# plug-v18.net
KiCad netlist of a schematic drawn in EAGLE
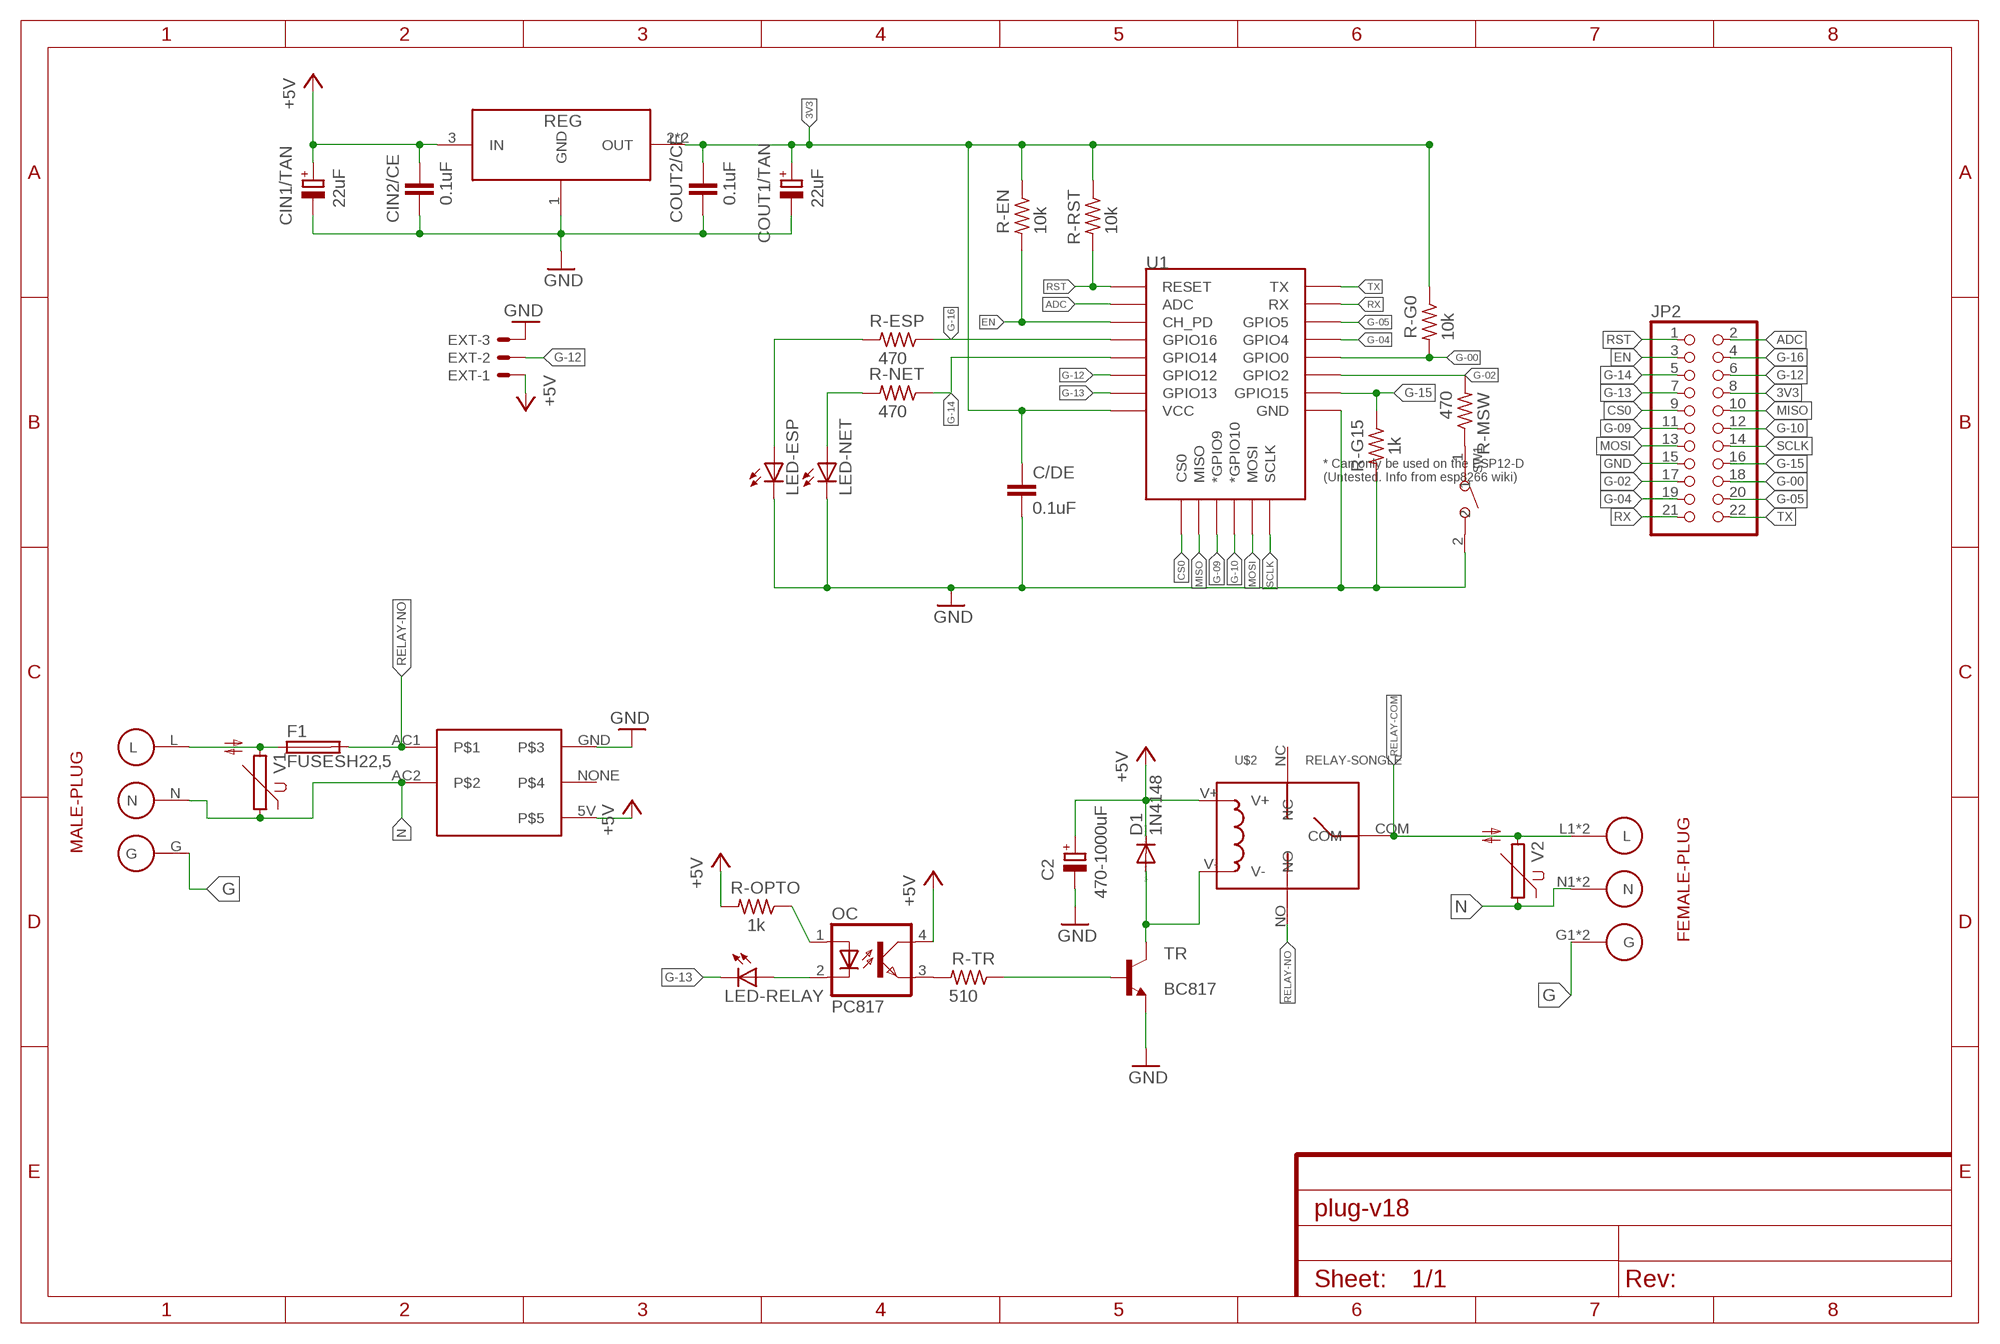
[diagram p0: schematic, sheet 1]

(export (version "E")
  (design (tool "Eeschema 10.0.6"))
  (components
    (comp (ref "C/DE")
      (value "0.1uF")
      (footprint "eagle-import:C0805")
      (libsource (lib "eagle-import") (part "C-EUC0805"))
    )
    (comp (ref "C2")
      (value "470-1000uF")
      (footprint "eagle-import:E3,5-8")
      (libsource (lib "eagle-import") (part "CPOL-EUE3.5-8"))
    )
    (comp (ref "CIN1/TAN")
      (value "22uF")
      (footprint "eagle-import:B_3528-21R")
      (libsource (lib "eagle-import") (part "CPOL-EUB/3528-21R"))
    )
    (comp (ref "CIN2/CE")
      (value "0.1uF")
      (footprint "eagle-import:C0805K")
      (libsource (lib "eagle-import") (part "C-EUC0805K"))
    )
    (comp (ref "COUT1/TAN")
      (value "22uF")
      (footprint "eagle-import:B_3528-21R")
      (libsource (lib "eagle-import") (part "CPOL-EUB/3528-21R"))
    )
    (comp (ref "COUT2/CE")
      (value "0.1uF")
      (footprint "eagle-import:C0805K")
      (libsource (lib "eagle-import") (part "C-EUC0805K"))
    )
    (comp (ref "D1")
      (value "1N4148")
      (footprint "eagle-import:DO35-7")
      (libsource (lib "eagle-import") (part "1N4148DO35-7"))
    )
    (comp (ref "EXT")
      (value "53048-03")
      (footprint "eagle-import:53048-03")
      (fields (field (name "MF") "WALDOM/MOLEX") (field (name "MPN") "53048-0310"))
      (libsource (lib "eagle-import") (part "53?-03048"))
    )
    (comp (ref "F1")
      (value "FUSESH22,5")
      (footprint "eagle-import:SH22,5")
      (libsource (lib "eagle-import") (part "FUSESH22,5"))
    )
    (comp (ref "JP2")
      (value "PINHD-2X11")
      (footprint "eagle-import:2X11")
      (libsource (lib "eagle-import") (part "PINHD-2X11"))
    )
    (comp (ref "LED-ESP")
      (value "LEDCHIPLED_0805")
      (footprint "eagle-import:CHIPLED_0805")
      (libsource (lib "eagle-import") (part "LEDCHIPLED_0805"))
    )
    (comp (ref "LED-NET")
      (value "LEDCHIPLED_0805")
      (footprint "eagle-import:CHIPLED_0805")
      (libsource (lib "eagle-import") (part "LEDCHIPLED_0805"))
    )
    (comp (ref "LED-RELAY")
      (value "LEDCHIPLED_0805")
      (footprint "eagle-import:CHIPLED_0805")
      (libsource (lib "eagle-import") (part "LEDCHIPLED_0805"))
    )
    (comp (ref "OC")
      (value "PC817")
      (footprint "eagle-import:DIL04")
      (fields (field (name "MPN") "PC817X4J000F"))
      (libsource (lib "eagle-import") (part "PC817"))
    )
    (comp (ref "R-EN")
      (value "10k")
      (footprint "eagle-import:M0805")
      (libsource (lib "eagle-import") (part "R-US_M0805"))
    )
    (comp (ref "R-ESP")
      (value "470")
      (footprint "eagle-import:M0805")
      (libsource (lib "eagle-import") (part "R-US_M0805"))
    )
    (comp (ref "R-G0")
      (value "10k")
      (footprint "eagle-import:M0805")
      (libsource (lib "eagle-import") (part "R-US_M0805"))
    )
    (comp (ref "R-G15")
      (value "1k")
      (footprint "eagle-import:M0805")
      (libsource (lib "eagle-import") (part "R-US_M0805"))
    )
    (comp (ref "R-MSW")
      (value "470")
      (footprint "eagle-import:M0805")
      (libsource (lib "eagle-import") (part "R-US_M0805"))
    )
    (comp (ref "R-NET")
      (value "470")
      (footprint "eagle-import:M0805")
      (libsource (lib "eagle-import") (part "R-US_M0805"))
    )
    (comp (ref "R-OPTO")
      (value "1k")
      (footprint "eagle-import:M0805")
      (libsource (lib "eagle-import") (part "R-US_M0805"))
    )
    (comp (ref "R-RST")
      (value "10k")
      (footprint "eagle-import:M0805")
      (libsource (lib "eagle-import") (part "R-US_M0805"))
    )
    (comp (ref "R-TR")
      (value "510")
      (footprint "eagle-import:M0805")
      (libsource (lib "eagle-import") (part "R-US_M0805"))
    )
    (comp (ref "REG")
      (value "AMS1117-3.3")
      (footprint "eagle-import:SOT-223")
      (libsource (lib "eagle-import") (part "AMS1117-3.3"))
    )
    (comp (ref "SW1")
      (value "DIP-BUTTON(2P-6.0X3.0X4.3MM)-TS-1101F")
      (footprint "eagle-import:SW2-5.0-6.0X3.0X4.3MM")
      (libsource (lib "eagle-import") (part "DIP-BUTTON(2P-6.0X3.0X4.3MM)-TS-1101F"))
    )
    (comp (ref "TR")
      (value "BC817")
      (footprint "eagle-import:SOT23-BEC")
      (libsource (lib "eagle-import") (part "BC817SMD-16"))
    )
    (comp (ref "U$2")
      (value "RELAY-SONGLE")
      (footprint "eagle-import:RELAY-SONGLE")
      (libsource (lib "eagle-import") (part "RELAY-SONGLE"))
    )
    (comp (ref "U$3")
      (value "MALE-PLUG")
      (footprint "eagle-import:MALE-PLUG")
      (libsource (lib "eagle-import") (part "MALE-PLUG"))
    )
    (comp (ref "U$4")
      (value "POWERSUPPLY-5V-700MA")
      (footprint "eagle-import:POWERSUPPLY-5V-700MA")
      (libsource (lib "eagle-import") (part "POWERSUPPLY-5V-700MA"))
    )
    (comp (ref "U$5")
      (value "FEMALE-PLUG")
      (footprint "eagle-import:FEMALE-PLUG")
      (libsource (lib "eagle-import") (part "FEMALE-PLUG"))
    )
    (comp (ref "U1")
      (value "ESP12ESMD")
      (footprint "eagle-import:ESP12E-SMD")
      (libsource (lib "eagle-import") (part "ESP12ESMD"))
    )
    (comp (ref "V1")
      (value "S14K11")
      (footprint "eagle-import:S14K11")
      (libsource (lib "eagle-import") (part "S14K11"))
    )
    (comp (ref "V2")
      (value "S14K11")
      (footprint "eagle-import:S14K11")
      (libsource (lib "eagle-import") (part "S14K11"))
    )
  )
  (nets
    (net (code "1") (name "+5V") (class "Default")
      (node (ref "C2") (pin "+") (pinfunction "+_+") (pintype "passive"))
      (node (ref "CIN1/TAN") (pin "+") (pinfunction "+_+") (pintype "passive"))
      (node (ref "CIN2/CE") (pin "1") (pinfunction "1_1") (pintype "passive"))
      (node (ref "D1") (pin "C") (pinfunction "C_C") (pintype "passive"))
      (node (ref "EXT") (pin "1") (pinfunction "S_1") (pintype "passive"))
      (node (ref "OC") (pin "4") (pinfunction "COL_4") (pintype "passive"))
      (node (ref "R-OPTO") (pin "2") (pinfunction "2_2") (pintype "passive"))
      (node (ref "REG") (pin "3") (pinfunction "IN_3") (pintype "input"))
      (node (ref "U$2") (pin "V+") (pinfunction "V+_V+") (pintype "bidirectional"))
      (node (ref "U$4") (pin "5V") (pinfunction "P$5_5V") (pintype "bidirectional"))
    )
    (net (code "2") (name "3V3") (class "Default")
      (node (ref "C/DE") (pin "1") (pinfunction "1_1") (pintype "passive"))
      (node (ref "COUT1/TAN") (pin "+") (pinfunction "+_+") (pintype "passive"))
      (node (ref "COUT2/CE") (pin "1") (pinfunction "1_1") (pintype "passive"))
      (node (ref "JP2") (pin "8") (pinfunction "8_8") (pintype "passive"))
      (node (ref "R-EN") (pin "1") (pinfunction "1_1") (pintype "passive"))
      (node (ref "R-G0") (pin "1") (pinfunction "1_1") (pintype "passive"))
      (node (ref "R-RST") (pin "1") (pinfunction "1_1") (pintype "passive"))
      (node (ref "REG") (pin "2") (pinfunction "OUT_2") (pintype "output"))
      (node (ref "REG") (pin "4") (pinfunction "OUT_4") (pintype "output"))
      (node (ref "U1") (pin "VCC") (pinfunction "VCC_VCC") (pintype "bidirectional"))
    )
    (net (code "3") (name "ADC") (class "Default")
      (node (ref "JP2") (pin "2") (pinfunction "2_2") (pintype "passive"))
      (node (ref "U1") (pin "ADC") (pinfunction "ADC_ADC") (pintype "bidirectional"))
    )
    (net (code "4") (name "CS0") (class "Default")
      (node (ref "JP2") (pin "9") (pinfunction "9_9") (pintype "passive"))
      (node (ref "U1") (pin "CS0") (pinfunction "CS0_CS0") (pintype "bidirectional"))
    )
    (net (code "5") (name "EN") (class "Default")
      (node (ref "JP2") (pin "3") (pinfunction "3_3") (pintype "passive"))
      (node (ref "R-EN") (pin "2") (pinfunction "2_2") (pintype "passive"))
      (node (ref "U1") (pin "CH_PD") (pinfunction "CH_PD_CH_PD") (pintype "bidirectional"))
    )
    (net (code "6") (name "G") (class "Default")
      (node (ref "U$3") (pin "G") (pinfunction "G_G") (pintype "bidirectional"))
      (node (ref "U$5") (pin "G1") (pinfunction "G_G1") (pintype "bidirectional"))
      (node (ref "U$5") (pin "G2") (pinfunction "G_G2") (pintype "bidirectional"))
    )
    (net (code "7") (name "G-00") (class "Default")
      (node (ref "JP2") (pin "18") (pinfunction "18_18") (pintype "passive"))
      (node (ref "R-G0") (pin "2") (pinfunction "2_2") (pintype "passive"))
      (node (ref "U1") (pin "GPIO0") (pinfunction "GPIO0_GPIO0") (pintype "bidirectional"))
    )
    (net (code "8") (name "G-02") (class "Default")
      (node (ref "JP2") (pin "17") (pinfunction "17_17") (pintype "passive"))
      (node (ref "R-MSW") (pin "2") (pinfunction "2_2") (pintype "passive"))
      (node (ref "U1") (pin "GPIO2") (pinfunction "GPIO2_GPIO2") (pintype "bidirectional"))
    )
    (net (code "9") (name "G-04") (class "Default")
      (node (ref "JP2") (pin "19") (pinfunction "19_19") (pintype "passive"))
      (node (ref "U1") (pin "GPIO4") (pinfunction "GPIO4_GPIO4") (pintype "bidirectional"))
    )
    (net (code "10") (name "G-05") (class "Default")
      (node (ref "JP2") (pin "20") (pinfunction "20_20") (pintype "passive"))
      (node (ref "U1") (pin "GPIO5") (pinfunction "GPIO5_GPIO5") (pintype "bidirectional"))
    )
    (net (code "11") (name "G-09") (class "Default")
      (node (ref "JP2") (pin "11") (pinfunction "11_11") (pintype "passive"))
      (node (ref "U1") (pin "GPIO9") (pinfunction "*GPIO9_GPIO9") (pintype "bidirectional"))
    )
    (net (code "12") (name "G-10") (class "Default")
      (node (ref "JP2") (pin "12") (pinfunction "12_12") (pintype "passive"))
      (node (ref "U1") (pin "GPIO10") (pinfunction "*GPIO10_GPIO10") (pintype "bidirectional"))
    )
    (net (code "13") (name "G-12") (class "Default")
      (node (ref "EXT") (pin "2") (pinfunction "S_2") (pintype "passive"))
      (node (ref "JP2") (pin "6") (pinfunction "6_6") (pintype "passive"))
      (node (ref "U1") (pin "GPIO12") (pinfunction "GPIO12_GPIO12") (pintype "bidirectional"))
    )
    (net (code "14") (name "G-13") (class "Default")
      (node (ref "JP2") (pin "7") (pinfunction "7_7") (pintype "passive"))
      (node (ref "LED-RELAY") (pin "C") (pinfunction "C_C") (pintype "passive"))
      (node (ref "U1") (pin "GPIO13") (pinfunction "GPIO13_GPIO13") (pintype "bidirectional"))
    )
    (net (code "15") (name "G-14") (class "Default")
      (node (ref "JP2") (pin "5") (pinfunction "5_5") (pintype "passive"))
      (node (ref "R-NET") (pin "1") (pinfunction "1_1") (pintype "passive"))
      (node (ref "U1") (pin "GPIO14") (pinfunction "GPIO14_GPIO14") (pintype "bidirectional"))
    )
    (net (code "16") (name "G-15") (class "Default")
      (node (ref "JP2") (pin "16") (pinfunction "16_16") (pintype "passive"))
      (node (ref "R-G15") (pin "1") (pinfunction "1_1") (pintype "passive"))
      (node (ref "U1") (pin "GPIO15") (pinfunction "GPIO15_GPIO15") (pintype "bidirectional"))
    )
    (net (code "17") (name "G-16") (class "Default")
      (node (ref "JP2") (pin "4") (pinfunction "4_4") (pintype "passive"))
      (node (ref "R-ESP") (pin "1") (pinfunction "1_1") (pintype "passive"))
      (node (ref "U1") (pin "GPIO16") (pinfunction "GPIO16_GPIO16") (pintype "bidirectional"))
    )
    (net (code "18") (name "GND") (class "Default")
      (node (ref "C/DE") (pin "2") (pinfunction "2_2") (pintype "passive"))
      (node (ref "C2") (pin "-") (pinfunction "-_-") (pintype "passive"))
      (node (ref "CIN1/TAN") (pin "-") (pinfunction "-_-") (pintype "passive"))
      (node (ref "CIN2/CE") (pin "2") (pinfunction "2_2") (pintype "passive"))
      (node (ref "COUT1/TAN") (pin "-") (pinfunction "-_-") (pintype "passive"))
      (node (ref "COUT2/CE") (pin "2") (pinfunction "2_2") (pintype "passive"))
      (node (ref "EXT") (pin "3") (pinfunction "S_3") (pintype "passive"))
      (node (ref "JP2") (pin "15") (pinfunction "15_15") (pintype "passive"))
      (node (ref "LED-ESP") (pin "C") (pinfunction "C_C") (pintype "passive"))
      (node (ref "LED-NET") (pin "C") (pinfunction "C_C") (pintype "passive"))
      (node (ref "R-G15") (pin "2") (pinfunction "2_2") (pintype "passive"))
      (node (ref "REG") (pin "1") (pinfunction "GND_1") (pintype "passive"))
      (node (ref "SW1") (pin "2") (pinfunction "2_2") (pintype "bidirectional"))
      (node (ref "TR") (pin "E") (pinfunction "E_E") (pintype "passive"))
      (node (ref "U$4") (pin "GND") (pinfunction "P$3_GND") (pintype "bidirectional"))
      (node (ref "U1") (pin "GND") (pinfunction "GND_GND") (pintype "bidirectional"))
    )
    (net (code "19") (name "MISO") (class "Default")
      (node (ref "JP2") (pin "10") (pinfunction "10_10") (pintype "passive"))
      (node (ref "U1") (pin "MISO") (pinfunction "MISO_MISO") (pintype "bidirectional"))
    )
    (net (code "20") (name "MOSI") (class "Default")
      (node (ref "JP2") (pin "13") (pinfunction "13_13") (pintype "passive"))
      (node (ref "U1") (pin "MOSI") (pinfunction "MOSI_MOSI") (pintype "bidirectional"))
    )
    (net (code "21") (name "N") (class "Default")
      (node (ref "U$3") (pin "N") (pinfunction "N_N") (pintype "bidirectional"))
      (node (ref "U$4") (pin "AC2") (pinfunction "P$2_AC2") (pintype "bidirectional"))
      (node (ref "U$5") (pin "N1") (pinfunction "N_N1") (pintype "bidirectional"))
      (node (ref "U$5") (pin "N2") (pinfunction "N_N2") (pintype "bidirectional"))
      (node (ref "V1") (pin "1") (pinfunction "1_1") (pintype "passive"))
      (node (ref "V2") (pin "1") (pinfunction "1_1") (pintype "passive"))
    )
    (net (code "22") (name "Net-(D1-PadA)") (class "Default")
      (node (ref "D1") (pin "A") (pinfunction "A_A") (pintype "passive"))
      (node (ref "TR") (pin "C") (pinfunction "C_C") (pintype "passive"))
      (node (ref "U$2") (pin "V-") (pinfunction "V-_V-") (pintype "bidirectional"))
    )
    (net (code "23") (name "Net-(F1-Pad1)") (class "Default")
      (node (ref "F1") (pin "1") (pinfunction "1_1") (pintype "passive"))
      (node (ref "U$3") (pin "L") (pinfunction "L_L") (pintype "bidirectional"))
      (node (ref "V1") (pin "2") (pinfunction "2_2") (pintype "passive"))
    )
    (net (code "24") (name "Net-(LED-ESP-PadA)") (class "Default")
      (node (ref "LED-ESP") (pin "A") (pinfunction "A_A") (pintype "passive"))
      (node (ref "R-ESP") (pin "2") (pinfunction "2_2") (pintype "passive"))
    )
    (net (code "25") (name "Net-(LED-NET-PadA)") (class "Default")
      (node (ref "LED-NET") (pin "A") (pinfunction "A_A") (pintype "passive"))
      (node (ref "R-NET") (pin "2") (pinfunction "2_2") (pintype "passive"))
    )
    (net (code "26") (name "Net-(OC-A)") (class "Default")
      (node (ref "OC") (pin "1") (pinfunction "A_1") (pintype "passive"))
      (node (ref "R-OPTO") (pin "1") (pinfunction "1_1") (pintype "passive"))
    )
    (net (code "27") (name "Net-(OC-C)") (class "Default")
      (node (ref "LED-RELAY") (pin "A") (pinfunction "A_A") (pintype "passive"))
      (node (ref "OC") (pin "2") (pinfunction "C_2") (pintype "passive"))
    )
    (net (code "28") (name "Net-(OC-EMIT)") (class "Default")
      (node (ref "OC") (pin "3") (pinfunction "EMIT_3") (pintype "passive"))
      (node (ref "R-TR") (pin "2") (pinfunction "2_2") (pintype "passive"))
    )
    (net (code "29") (name "Net-(R-MSW-Pad1)") (class "Default")
      (node (ref "R-MSW") (pin "1") (pinfunction "1_1") (pintype "passive"))
      (node (ref "SW1") (pin "1") (pinfunction "1_1") (pintype "bidirectional"))
    )
    (net (code "30") (name "Net-(R-TR-Pad1)") (class "Default")
      (node (ref "R-TR") (pin "1") (pinfunction "1_1") (pintype "passive"))
      (node (ref "TR") (pin "B") (pinfunction "B_B") (pintype "passive"))
    )
    (net (code "31") (name "RELAY-COM") (class "Default")
      (node (ref "U$2") (pin "COM") (pinfunction "COM_COM") (pintype "bidirectional"))
      (node (ref "U$5") (pin "L1") (pinfunction "L_L1") (pintype "bidirectional"))
      (node (ref "U$5") (pin "L2") (pinfunction "L_L2") (pintype "bidirectional"))
      (node (ref "V2") (pin "2") (pinfunction "2_2") (pintype "passive"))
    )
    (net (code "32") (name "RELAY-NO") (class "Default")
      (node (ref "F1") (pin "2") (pinfunction "2_2") (pintype "passive"))
      (node (ref "U$2") (pin "NO") (pinfunction "NO_NO") (pintype "bidirectional"))
      (node (ref "U$4") (pin "AC1") (pinfunction "P$1_AC1") (pintype "bidirectional"))
    )
    (net (code "33") (name "RST") (class "Default")
      (node (ref "JP2") (pin "1") (pinfunction "1_1") (pintype "passive"))
      (node (ref "R-RST") (pin "2") (pinfunction "2_2") (pintype "passive"))
      (node (ref "U1") (pin "RESET") (pinfunction "RESET_RESET") (pintype "bidirectional"))
    )
    (net (code "34") (name "RX") (class "Default")
      (node (ref "JP2") (pin "21") (pinfunction "21_21") (pintype "passive"))
      (node (ref "U1") (pin "RXD0") (pinfunction "RX_RXD0") (pintype "bidirectional"))
    )
    (net (code "35") (name "SCLK") (class "Default")
      (node (ref "JP2") (pin "14") (pinfunction "14_14") (pintype "passive"))
      (node (ref "U1") (pin "SCLK") (pinfunction "SCLK_SCLK") (pintype "bidirectional"))
    )
    (net (code "36") (name "TX") (class "Default")
      (node (ref "JP2") (pin "22") (pinfunction "22_22") (pintype "passive"))
      (node (ref "U1") (pin "TXD0") (pinfunction "TX_TXD0") (pintype "bidirectional"))
    )
    (net (code "37") (name "unconnected-(U$2-PadNC)") (class "Default")
      (node (ref "U$2") (pin "NC") (pinfunction "NC_NC") (pintype "bidirectional"))
    )
    (net (code "38") (name "unconnected-(U$4-P$4-PadNONE)") (class "Default")
      (node (ref "U$4") (pin "NONE") (pinfunction "P$4_NONE") (pintype "bidirectional"))
    )
  )
)
